# Button_V0_2.net
KiCad netlist of a schematic drawn in EAGLE
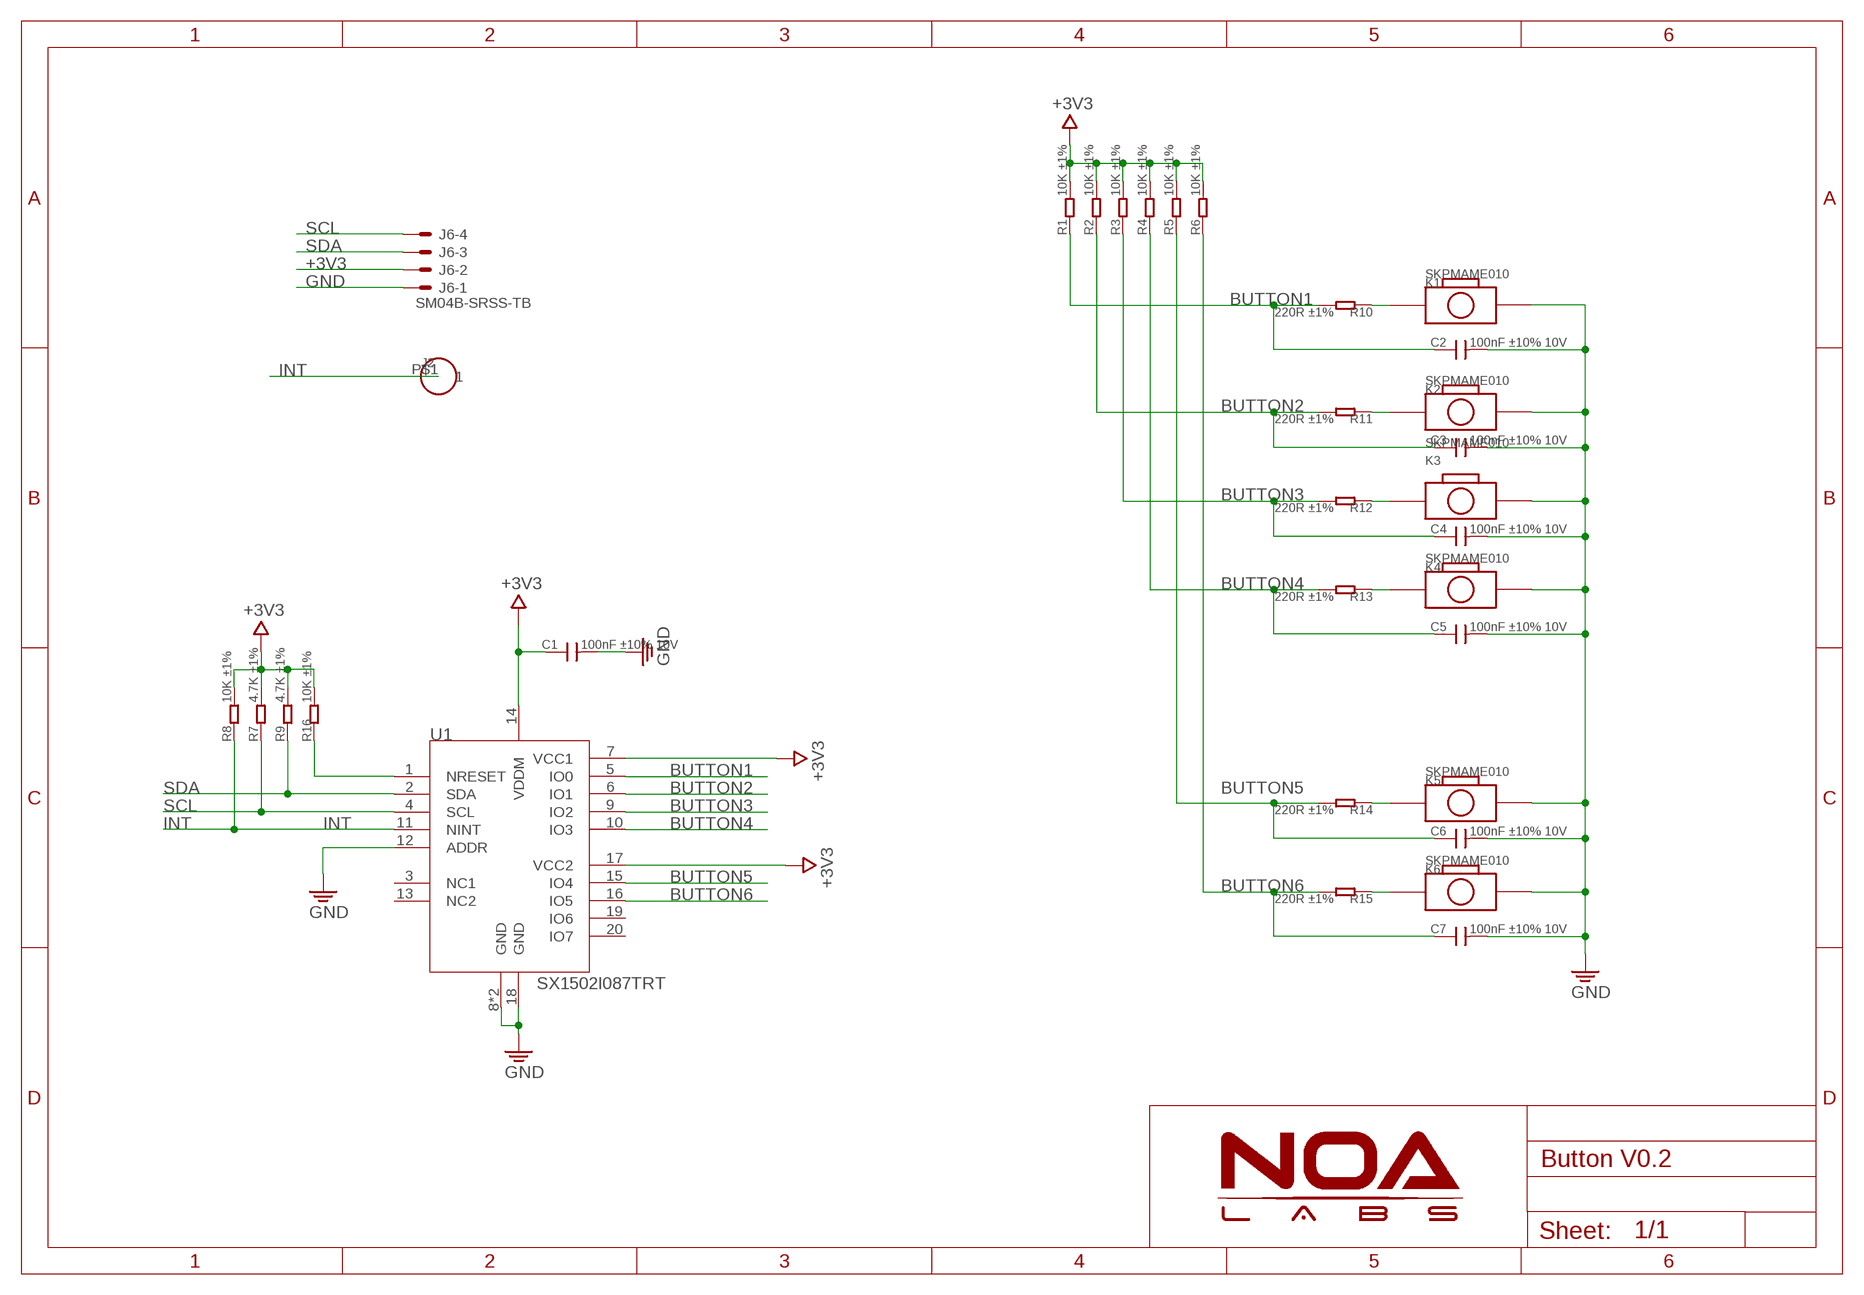
[diagram p0: schematic, sheet 1]

(export (version "E")
  (design (tool "Eeschema 10.0.6"))
  (components
    (comp (ref "C1")
      (value "100nF ±10% 10V")
      (footprint "eagle-import:C0402")
      (libsource (lib "eagle-import") (part "C-0402"))
    )
    (comp (ref "C2")
      (value "100nF ±10% 10V")
      (footprint "eagle-import:C0402")
      (libsource (lib "eagle-import") (part "C-0402"))
    )
    (comp (ref "C3")
      (value "100nF ±10% 10V")
      (footprint "eagle-import:C0402")
      (libsource (lib "eagle-import") (part "C-0402"))
    )
    (comp (ref "C4")
      (value "100nF ±10% 10V")
      (footprint "eagle-import:C0402")
      (libsource (lib "eagle-import") (part "C-0402"))
    )
    (comp (ref "C5")
      (value "100nF ±10% 10V")
      (footprint "eagle-import:C0402")
      (libsource (lib "eagle-import") (part "C-0402"))
    )
    (comp (ref "C6")
      (value "100nF ±10% 10V")
      (footprint "eagle-import:C0402")
      (libsource (lib "eagle-import") (part "C-0402"))
    )
    (comp (ref "C7")
      (value "100nF ±10% 10V")
      (footprint "eagle-import:C0402")
      (libsource (lib "eagle-import") (part "C-0402"))
    )
    (comp (ref "J2")
      (value "HEADER-1P-32")
      (footprint "eagle-import:1P-60_32MIL")
      (libsource (lib "eagle-import") (part "HEADER-1P-32"))
    )
    (comp (ref "J6")
      (value "SM04B-SRSS-TB")
      (footprint "eagle-import:SM04B-SRSS-TB")
      (libsource (lib "eagle-import") (part "?M04B-SRSS-TBS"))
    )
    (comp (ref "K1")
      (value "SKPMAME010")
      (footprint "eagle-import:SKPMAME010")
      (libsource (lib "eagle-import") (part "BUTTON-2PSKPMAME010"))
    )
    (comp (ref "K2")
      (value "SKPMAME010")
      (footprint "eagle-import:SKPMAME010")
      (libsource (lib "eagle-import") (part "BUTTON-2PSKPMAME010"))
    )
    (comp (ref "K3")
      (value "SKPMAME010")
      (footprint "eagle-import:SKPMAME010")
      (libsource (lib "eagle-import") (part "BUTTON-2PSKPMAME010"))
    )
    (comp (ref "K4")
      (value "SKPMAME010")
      (footprint "eagle-import:SKPMAME010")
      (libsource (lib "eagle-import") (part "BUTTON-2PSKPMAME010"))
    )
    (comp (ref "K5")
      (value "SKPMAME010")
      (footprint "eagle-import:SKPMAME010")
      (libsource (lib "eagle-import") (part "BUTTON-2PSKPMAME010"))
    )
    (comp (ref "K6")
      (value "SKPMAME010")
      (footprint "eagle-import:SKPMAME010")
      (libsource (lib "eagle-import") (part "BUTTON-2PSKPMAME010"))
    )
    (comp (ref "R1")
      (value "10K ±1%")
      (footprint "eagle-import:R0402")
      (libsource (lib "eagle-import") (part "R-0402"))
    )
    (comp (ref "R2")
      (value "10K ±1%")
      (footprint "eagle-import:R0402")
      (libsource (lib "eagle-import") (part "R-0402"))
    )
    (comp (ref "R3")
      (value "10K ±1%")
      (footprint "eagle-import:R0402")
      (libsource (lib "eagle-import") (part "R-0402"))
    )
    (comp (ref "R4")
      (value "10K ±1%")
      (footprint "eagle-import:R0402")
      (libsource (lib "eagle-import") (part "R-0402"))
    )
    (comp (ref "R5")
      (value "10K ±1%")
      (footprint "eagle-import:R0402")
      (libsource (lib "eagle-import") (part "R-0402"))
    )
    (comp (ref "R6")
      (value "10K ±1%")
      (footprint "eagle-import:R0402")
      (libsource (lib "eagle-import") (part "R-0402"))
    )
    (comp (ref "R7")
      (value "4.7K ±1%")
      (footprint "eagle-import:R0402")
      (libsource (lib "eagle-import") (part "R-0402"))
    )
    (comp (ref "R8")
      (value "10K ±1%")
      (footprint "eagle-import:R0402")
      (libsource (lib "eagle-import") (part "R-0402"))
    )
    (comp (ref "R9")
      (value "4.7K ±1%")
      (footprint "eagle-import:R0402")
      (libsource (lib "eagle-import") (part "R-0402"))
    )
    (comp (ref "R10")
      (value "220R ±1%")
      (footprint "eagle-import:R0402")
      (libsource (lib "eagle-import") (part "R-0402"))
    )
    (comp (ref "R11")
      (value "220R ±1%")
      (footprint "eagle-import:R0402")
      (libsource (lib "eagle-import") (part "R-0402"))
    )
    (comp (ref "R12")
      (value "220R ±1%")
      (footprint "eagle-import:R0402")
      (libsource (lib "eagle-import") (part "R-0402"))
    )
    (comp (ref "R13")
      (value "220R ±1%")
      (footprint "eagle-import:R0402")
      (libsource (lib "eagle-import") (part "R-0402"))
    )
    (comp (ref "R14")
      (value "220R ±1%")
      (footprint "eagle-import:R0402")
      (libsource (lib "eagle-import") (part "R-0402"))
    )
    (comp (ref "R15")
      (value "220R ±1%")
      (footprint "eagle-import:R0402")
      (libsource (lib "eagle-import") (part "R-0402"))
    )
    (comp (ref "R16")
      (value "10K ±1%")
      (footprint "eagle-import:R0402")
      (libsource (lib "eagle-import") (part "R-0402"))
    )
    (comp (ref "U1")
      (value "SX1502I087TRT")
      (footprint "eagle-import:QFN-20-3X3MM")
      (libsource (lib "eagle-import") (part "SX1502"))
    )
  )
  (nets
    (net (code "1") (name "+3V3") (class "Default")
      (node (ref "C1") (pin "1") (pinfunction "1_1") (pintype "passive"))
      (node (ref "J6") (pin "2") (pinfunction "S_2") (pintype "passive"))
      (node (ref "R1") (pin "2") (pinfunction "2_2") (pintype "passive"))
      (node (ref "R16") (pin "2") (pinfunction "2_2") (pintype "passive"))
      (node (ref "R2") (pin "2") (pinfunction "2_2") (pintype "passive"))
      (node (ref "R3") (pin "2") (pinfunction "2_2") (pintype "passive"))
      (node (ref "R4") (pin "2") (pinfunction "2_2") (pintype "passive"))
      (node (ref "R5") (pin "2") (pinfunction "2_2") (pintype "passive"))
      (node (ref "R6") (pin "2") (pinfunction "2_2") (pintype "passive"))
      (node (ref "R7") (pin "2") (pinfunction "2_2") (pintype "passive"))
      (node (ref "R8") (pin "2") (pinfunction "2_2") (pintype "passive"))
      (node (ref "R9") (pin "2") (pinfunction "2_2") (pintype "passive"))
      (node (ref "U1") (pin "14") (pinfunction "VDDM_14") (pintype "bidirectional"))
      (node (ref "U1") (pin "17") (pinfunction "VCC2_17") (pintype "bidirectional"))
      (node (ref "U1") (pin "7") (pinfunction "VCC1_7") (pintype "bidirectional"))
    )
    (net (code "2") (name "/BUTTON1") (class "Default")
      (node (ref "C2") (pin "1") (pinfunction "1_1") (pintype "passive"))
      (node (ref "R1") (pin "1") (pinfunction "1_1") (pintype "passive"))
      (node (ref "R10") (pin "2") (pinfunction "2_2") (pintype "passive"))
      (node (ref "U1") (pin "5") (pinfunction "IO0_5") (pintype "bidirectional"))
    )
    (net (code "3") (name "/BUTTON2") (class "Default")
      (node (ref "C3") (pin "1") (pinfunction "1_1") (pintype "passive"))
      (node (ref "R11") (pin "2") (pinfunction "2_2") (pintype "passive"))
      (node (ref "R2") (pin "1") (pinfunction "1_1") (pintype "passive"))
      (node (ref "U1") (pin "6") (pinfunction "IO1_6") (pintype "bidirectional"))
    )
    (net (code "4") (name "/BUTTON3") (class "Default")
      (node (ref "C4") (pin "1") (pinfunction "1_1") (pintype "passive"))
      (node (ref "R12") (pin "2") (pinfunction "2_2") (pintype "passive"))
      (node (ref "R3") (pin "1") (pinfunction "1_1") (pintype "passive"))
      (node (ref "U1") (pin "9") (pinfunction "IO2_9") (pintype "bidirectional"))
    )
    (net (code "5") (name "/BUTTON4") (class "Default")
      (node (ref "C5") (pin "1") (pinfunction "1_1") (pintype "passive"))
      (node (ref "R13") (pin "2") (pinfunction "2_2") (pintype "passive"))
      (node (ref "R4") (pin "1") (pinfunction "1_1") (pintype "passive"))
      (node (ref "U1") (pin "10") (pinfunction "IO3_10") (pintype "bidirectional"))
    )
    (net (code "6") (name "/BUTTON5") (class "Default")
      (node (ref "C6") (pin "1") (pinfunction "1_1") (pintype "passive"))
      (node (ref "R14") (pin "2") (pinfunction "2_2") (pintype "passive"))
      (node (ref "R5") (pin "1") (pinfunction "1_1") (pintype "passive"))
      (node (ref "U1") (pin "15") (pinfunction "IO4_15") (pintype "bidirectional"))
    )
    (net (code "7") (name "/BUTTON6") (class "Default")
      (node (ref "C7") (pin "1") (pinfunction "1_1") (pintype "passive"))
      (node (ref "R15") (pin "2") (pinfunction "2_2") (pintype "passive"))
      (node (ref "R6") (pin "1") (pinfunction "1_1") (pintype "passive"))
      (node (ref "U1") (pin "16") (pinfunction "IO5_16") (pintype "bidirectional"))
    )
    (net (code "8") (name "/INT") (class "Default")
      (node (ref "J2") (pin "P$1") (pinfunction "1_P$1") (pintype "bidirectional"))
      (node (ref "R8") (pin "1") (pinfunction "1_1") (pintype "passive"))
      (node (ref "U1") (pin "11") (pinfunction "NINT_11") (pintype "bidirectional"))
    )
    (net (code "9") (name "/SCL") (class "Default")
      (node (ref "J6") (pin "4") (pinfunction "S_4") (pintype "passive"))
      (node (ref "R7") (pin "1") (pinfunction "1_1") (pintype "passive"))
      (node (ref "U1") (pin "4") (pinfunction "SCL_4") (pintype "bidirectional"))
    )
    (net (code "10") (name "/SDA") (class "Default")
      (node (ref "J6") (pin "3") (pinfunction "S_3") (pintype "passive"))
      (node (ref "R9") (pin "1") (pinfunction "1_1") (pintype "passive"))
      (node (ref "U1") (pin "2") (pinfunction "SDA_2") (pintype "bidirectional"))
    )
    (net (code "11") (name "GND") (class "Default")
      (node (ref "C1") (pin "2") (pinfunction "2_2") (pintype "passive"))
      (node (ref "C2") (pin "2") (pinfunction "2_2") (pintype "passive"))
      (node (ref "C3") (pin "2") (pinfunction "2_2") (pintype "passive"))
      (node (ref "C4") (pin "2") (pinfunction "2_2") (pintype "passive"))
      (node (ref "C5") (pin "2") (pinfunction "2_2") (pintype "passive"))
      (node (ref "C6") (pin "2") (pinfunction "2_2") (pintype "passive"))
      (node (ref "C7") (pin "2") (pinfunction "2_2") (pintype "passive"))
      (node (ref "J6") (pin "1") (pinfunction "S_1") (pintype "passive"))
      (node (ref "K1") (pin "2") (pinfunction "2_2") (pintype "bidirectional"))
      (node (ref "K2") (pin "2") (pinfunction "2_2") (pintype "bidirectional"))
      (node (ref "K3") (pin "2") (pinfunction "2_2") (pintype "bidirectional"))
      (node (ref "K4") (pin "2") (pinfunction "2_2") (pintype "bidirectional"))
      (node (ref "K5") (pin "2") (pinfunction "2_2") (pintype "bidirectional"))
      (node (ref "K6") (pin "2") (pinfunction "2_2") (pintype "bidirectional"))
      (node (ref "U1") (pin "12") (pinfunction "ADDR_12") (pintype "bidirectional"))
      (node (ref "U1") (pin "18") (pinfunction "GND_18") (pintype "bidirectional"))
      (node (ref "U1") (pin "21") (pinfunction "GND_21") (pintype "bidirectional"))
      (node (ref "U1") (pin "8") (pinfunction "GND_8") (pintype "bidirectional"))
    )
    (net (code "12") (name "Net-(K1-Pad1)") (class "Default")
      (node (ref "K1") (pin "1") (pinfunction "1_1") (pintype "bidirectional"))
      (node (ref "R10") (pin "1") (pinfunction "1_1") (pintype "passive"))
    )
    (net (code "13") (name "Net-(K2-Pad1)") (class "Default")
      (node (ref "K2") (pin "1") (pinfunction "1_1") (pintype "bidirectional"))
      (node (ref "R11") (pin "1") (pinfunction "1_1") (pintype "passive"))
    )
    (net (code "14") (name "Net-(K3-Pad1)") (class "Default")
      (node (ref "K3") (pin "1") (pinfunction "1_1") (pintype "bidirectional"))
      (node (ref "R12") (pin "1") (pinfunction "1_1") (pintype "passive"))
    )
    (net (code "15") (name "Net-(K4-Pad1)") (class "Default")
      (node (ref "K4") (pin "1") (pinfunction "1_1") (pintype "bidirectional"))
      (node (ref "R13") (pin "1") (pinfunction "1_1") (pintype "passive"))
    )
    (net (code "16") (name "Net-(K5-Pad1)") (class "Default")
      (node (ref "K5") (pin "1") (pinfunction "1_1") (pintype "bidirectional"))
      (node (ref "R14") (pin "1") (pinfunction "1_1") (pintype "passive"))
    )
    (net (code "17") (name "Net-(K6-Pad1)") (class "Default")
      (node (ref "K6") (pin "1") (pinfunction "1_1") (pintype "bidirectional"))
      (node (ref "R15") (pin "1") (pinfunction "1_1") (pintype "passive"))
    )
    (net (code "18") (name "Net-(U1-NRESET)") (class "Default")
      (node (ref "R16") (pin "1") (pinfunction "1_1") (pintype "passive"))
      (node (ref "U1") (pin "1") (pinfunction "NRESET_1") (pintype "bidirectional"))
    )
    (net (code "19") (name "unconnected-(U1-IO6-Pad19)") (class "Default")
      (node (ref "U1") (pin "19") (pinfunction "IO6_19") (pintype "bidirectional"))
    )
    (net (code "20") (name "unconnected-(U1-IO7-Pad20)") (class "Default")
      (node (ref "U1") (pin "20") (pinfunction "IO7_20") (pintype "bidirectional"))
    )
    (net (code "21") (name "unconnected-(U1-NC1-Pad3)") (class "Default")
      (node (ref "U1") (pin "3") (pinfunction "NC1_3") (pintype "bidirectional"))
    )
    (net (code "22") (name "unconnected-(U1-NC2-Pad13)") (class "Default")
      (node (ref "U1") (pin "13") (pinfunction "NC2_13") (pintype "bidirectional"))
    )
  )
)
